# attiny_breakout.net
KiCad netlist of a schematic drawn in EAGLE
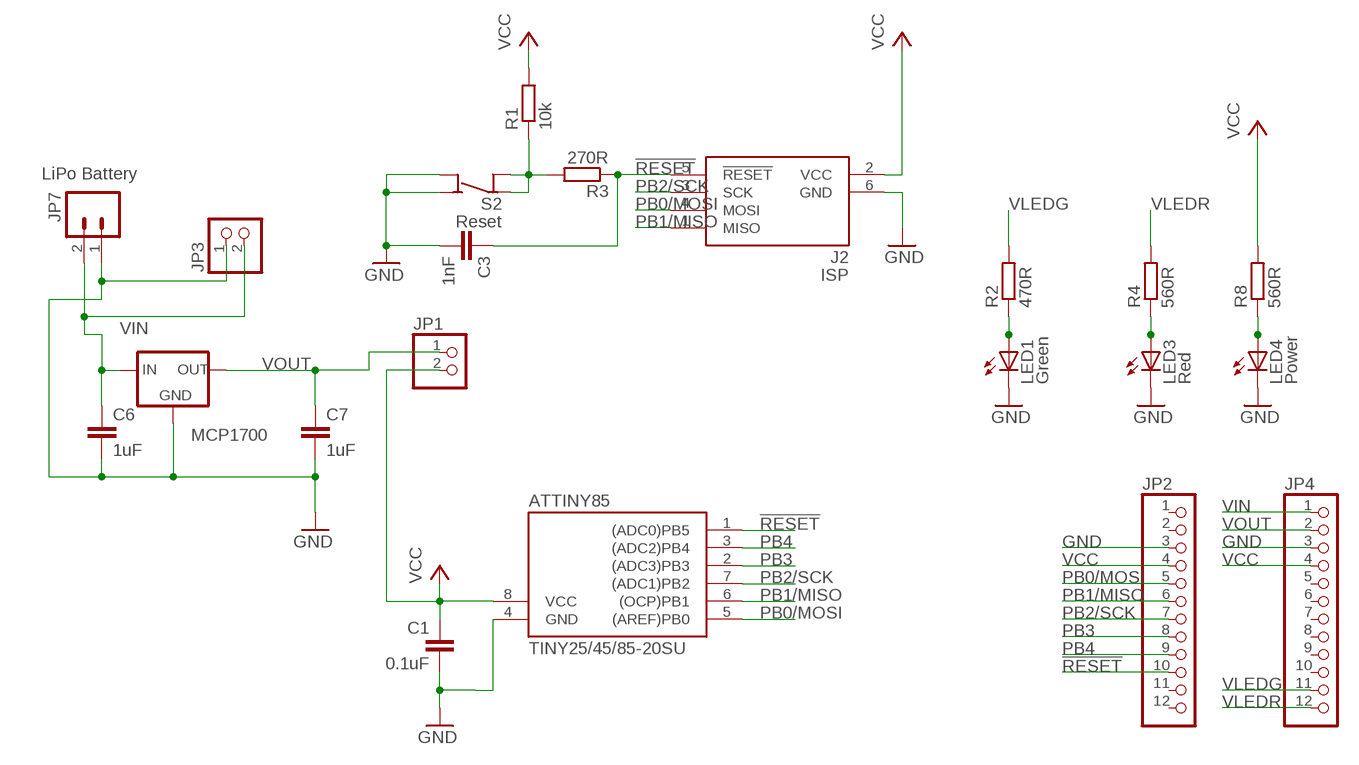
[diagram p0: schematic, sheet 1]

(export (version "E")
  (design (tool "Eeschema 10.0.6"))
  (components
    (comp (ref "ATTINY85")
      (value "TINY25/45/85-20SU")
      (footprint "eagle-import:SOIC8")
      (libsource (lib "eagle-import") (part "TINY25/45/85-20SU"))
    )
    (comp (ref "C1")
      (value "0.1uF")
      (footprint "eagle-import:C0805")
      (libsource (lib "eagle-import") (part "C-EUC0805"))
    )
    (comp (ref "C3")
      (value "1nF")
      (footprint "eagle-import:C0805")
      (libsource (lib "eagle-import") (part "C-EUC0805"))
    )
    (comp (ref "C6")
      (value "1uF")
      (footprint "eagle-import:C0805")
      (libsource (lib "eagle-import") (part "C-EUC0805"))
    )
    (comp (ref "C7")
      (value "1uF")
      (footprint "eagle-import:C0805")
      (libsource (lib "eagle-import") (part "C-EUC0805"))
    )
    (comp (ref "J2")
      (value "ISP")
      (footprint "eagle-import:CON6P2R")
      (libsource (lib "eagle-import") (part "AVRISP6"))
    )
    (comp (ref "JP1")
      (value "PINHD-1X2")
      (footprint "eagle-import:1X02")
      (libsource (lib "eagle-import") (part "PINHD-1X2"))
    )
    (comp (ref "JP2")
      (value "PINHD-1X12")
      (footprint "eagle-import:1X12")
      (libsource (lib "eagle-import") (part "PINHD-1X12"))
    )
    (comp (ref "JP3")
      (value "PINHD-1X2")
      (footprint "eagle-import:1X02")
      (libsource (lib "eagle-import") (part "PINHD-1X2"))
    )
    (comp (ref "JP4")
      (value "PINHD-1X12")
      (footprint "eagle-import:1X12")
      (libsource (lib "eagle-import") (part "PINHD-1X12"))
    )
    (comp (ref "JP7")
      (value "LiPo Battery")
      (footprint "eagle-import:JST-2-PTH")
      (libsource (lib "eagle-import") (part "M02JST-PTH-2"))
    )
    (comp (ref "LED1")
      (value "Green")
      (footprint "eagle-import:CHIP-LED0805")
      (libsource (lib "eagle-import") (part "LEDCHIP-LED0805"))
    )
    (comp (ref "LED3")
      (value "Red")
      (footprint "eagle-import:CHIP-LED0805")
      (libsource (lib "eagle-import") (part "LEDCHIP-LED0805"))
    )
    (comp (ref "LED4")
      (value "Power")
      (footprint "eagle-import:CHIP-LED0805")
      (libsource (lib "eagle-import") (part "LEDCHIP-LED0805"))
    )
    (comp (ref "MCP1700")
      (value "MCP1700")
      (footprint "eagle-import:SOT-23")
      (libsource (lib "eagle-import") (part "MCP1700SOT-23"))
    )
    (comp (ref "R1")
      (value "10k")
      (footprint "eagle-import:R0805")
      (libsource (lib "eagle-import") (part "R-EU_R0805"))
    )
    (comp (ref "R2")
      (value "470R")
      (footprint "eagle-import:R0805")
      (libsource (lib "eagle-import") (part "R-EU_R0805"))
    )
    (comp (ref "R3")
      (value "270R")
      (footprint "eagle-import:R0805")
      (libsource (lib "eagle-import") (part "R-EU_R0805"))
    )
    (comp (ref "R4")
      (value "560R")
      (footprint "eagle-import:R0805")
      (libsource (lib "eagle-import") (part "R-EU_R0805"))
    )
    (comp (ref "R8")
      (value "560R")
      (footprint "eagle-import:R0805")
      (libsource (lib "eagle-import") (part "R-EU_R0805"))
    )
    (comp (ref "S2")
      (value "Reset")
      (footprint "eagle-import:6MMTACTILE_4PIN")
      (libsource (lib "eagle-import") (part "SPST4"))
    )
  )
  (nets
    (net (code "1") (name "/PB0{slash}MOSI") (class "Default")
      (node (ref "ATTINY85") (pin "5") (pinfunction "(AREF)PB0_5") (pintype "bidirectional"))
      (node (ref "J2") (pin "4") (pinfunction "MOSI_4") (pintype "output"))
      (node (ref "JP2") (pin "5") (pinfunction "5_5") (pintype "passive"))
    )
    (net (code "2") (name "/PB1{slash}MISO") (class "Default")
      (node (ref "ATTINY85") (pin "6") (pinfunction "(OCP)PB1_6") (pintype "bidirectional"))
      (node (ref "J2") (pin "1") (pinfunction "MISO_1") (pintype "input"))
      (node (ref "JP2") (pin "6") (pinfunction "6_6") (pintype "passive"))
    )
    (net (code "3") (name "/PB2{slash}SCK") (class "Default")
      (node (ref "ATTINY85") (pin "7") (pinfunction "(ADC1)PB2_7") (pintype "bidirectional"))
      (node (ref "J2") (pin "3") (pinfunction "SCK_3") (pintype "output"))
      (node (ref "JP2") (pin "7") (pinfunction "7_7") (pintype "passive"))
    )
    (net (code "4") (name "/PB3") (class "Default")
      (node (ref "ATTINY85") (pin "2") (pinfunction "(ADC3)PB3_2") (pintype "bidirectional"))
      (node (ref "JP2") (pin "8") (pinfunction "8_8") (pintype "passive"))
    )
    (net (code "5") (name "/PB4") (class "Default")
      (node (ref "ATTINY85") (pin "3") (pinfunction "(ADC2)PB4_3") (pintype "bidirectional"))
      (node (ref "JP2") (pin "9") (pinfunction "9_9") (pintype "passive"))
    )
    (net (code "6") (name "/VIN") (class "Default")
      (node (ref "C6") (pin "1") (pinfunction "1_1") (pintype "passive"))
      (node (ref "JP3") (pin "2") (pinfunction "2_2") (pintype "passive"))
      (node (ref "JP4") (pin "1") (pinfunction "1_1") (pintype "passive"))
      (node (ref "JP7") (pin "2") (pinfunction "2_2") (pintype "passive"))
      (node (ref "MCP1700") (pin "3") (pinfunction "IN_3") (pintype "input"))
    )
    (net (code "7") (name "/VLEDG") (class "Default")
      (node (ref "JP4") (pin "11") (pinfunction "11_11") (pintype "passive"))
      (node (ref "R2") (pin "2") (pinfunction "2_2") (pintype "passive"))
    )
    (net (code "8") (name "/VLEDR") (class "Default")
      (node (ref "JP4") (pin "12") (pinfunction "12_12") (pintype "passive"))
      (node (ref "R4") (pin "2") (pinfunction "2_2") (pintype "passive"))
    )
    (net (code "9") (name "/VOUT") (class "Default")
      (node (ref "C7") (pin "1") (pinfunction "1_1") (pintype "passive"))
      (node (ref "JP1") (pin "1") (pinfunction "1_1") (pintype "passive"))
      (node (ref "JP4") (pin "2") (pinfunction "2_2") (pintype "passive"))
      (node (ref "MCP1700") (pin "2") (pinfunction "OUT_2") (pintype "passive"))
    )
    (net (code "10") (name "/~{RESET}") (class "Default")
      (node (ref "ATTINY85") (pin "1") (pinfunction "(ADC0)PB5_1") (pintype "bidirectional"))
      (node (ref "C3") (pin "1") (pinfunction "1_1") (pintype "passive"))
      (node (ref "J2") (pin "5") (pinfunction "~{RESET}_5") (pintype "output"))
      (node (ref "JP2") (pin "10") (pinfunction "10_10") (pintype "passive"))
      (node (ref "R3") (pin "1") (pinfunction "1_1") (pintype "passive"))
    )
    (net (code "11") (name "GND") (class "Default")
      (node (ref "ATTINY85") (pin "4") (pinfunction "GND_4") (pintype "power_in"))
      (node (ref "C1") (pin "2") (pinfunction "2_2") (pintype "passive"))
      (node (ref "C3") (pin "2") (pinfunction "2_2") (pintype "passive"))
      (node (ref "C6") (pin "2") (pinfunction "2_2") (pintype "passive"))
      (node (ref "C7") (pin "2") (pinfunction "2_2") (pintype "passive"))
      (node (ref "J2") (pin "6") (pinfunction "GND_6") (pintype "power_in"))
      (node (ref "JP2") (pin "3") (pinfunction "3_3") (pintype "passive"))
      (node (ref "JP3") (pin "1") (pinfunction "1_1") (pintype "passive"))
      (node (ref "JP4") (pin "3") (pinfunction "3_3") (pintype "passive"))
      (node (ref "JP7") (pin "1") (pinfunction "1_1") (pintype "passive"))
      (node (ref "LED1") (pin "C") (pinfunction "C_C") (pintype "passive"))
      (node (ref "LED3") (pin "C") (pinfunction "C_C") (pintype "passive"))
      (node (ref "LED4") (pin "C") (pinfunction "C_C") (pintype "passive"))
      (node (ref "MCP1700") (pin "1") (pinfunction "GND_1") (pintype "input"))
      (node (ref "S2") (pin "A1") (pinfunction "NO_A1") (pintype "passive"))
      (node (ref "S2") (pin "A2") (pinfunction "NO_A2") (pintype "passive"))
    )
    (net (code "12") (name "Net-(LED1-PadA)") (class "Default")
      (node (ref "LED1") (pin "A") (pinfunction "A_A") (pintype "passive"))
      (node (ref "R2") (pin "1") (pinfunction "1_1") (pintype "passive"))
    )
    (net (code "13") (name "Net-(LED3-PadA)") (class "Default")
      (node (ref "LED3") (pin "A") (pinfunction "A_A") (pintype "passive"))
      (node (ref "R4") (pin "1") (pinfunction "1_1") (pintype "passive"))
    )
    (net (code "14") (name "Net-(LED4-PadA)") (class "Default")
      (node (ref "LED4") (pin "A") (pinfunction "A_A") (pintype "passive"))
      (node (ref "R8") (pin "1") (pinfunction "1_1") (pintype "passive"))
    )
    (net (code "15") (name "Net-(R1-Pad1)") (class "Default")
      (node (ref "R1") (pin "1") (pinfunction "1_1") (pintype "passive"))
      (node (ref "R3") (pin "2") (pinfunction "2_2") (pintype "passive"))
      (node (ref "S2") (pin "B1") (pinfunction "COM_B1") (pintype "passive"))
      (node (ref "S2") (pin "B2") (pinfunction "COM_B2") (pintype "passive"))
    )
    (net (code "16") (name "VCC") (class "Default")
      (node (ref "ATTINY85") (pin "8") (pinfunction "VCC_8") (pintype "power_in"))
      (node (ref "C1") (pin "1") (pinfunction "1_1") (pintype "passive"))
      (node (ref "J2") (pin "2") (pinfunction "VCC_2") (pintype "power_in"))
      (node (ref "JP1") (pin "2") (pinfunction "2_2") (pintype "passive"))
      (node (ref "JP2") (pin "4") (pinfunction "4_4") (pintype "passive"))
      (node (ref "JP4") (pin "4") (pinfunction "4_4") (pintype "passive"))
      (node (ref "R1") (pin "2") (pinfunction "2_2") (pintype "passive"))
      (node (ref "R8") (pin "2") (pinfunction "2_2") (pintype "passive"))
    )
    (net (code "17") (name "unconnected-(JP2-Pad1)") (class "Default")
      (node (ref "JP2") (pin "1") (pinfunction "1_1") (pintype "passive"))
    )
    (net (code "18") (name "unconnected-(JP2-Pad2)") (class "Default")
      (node (ref "JP2") (pin "2") (pinfunction "2_2") (pintype "passive"))
    )
    (net (code "19") (name "unconnected-(JP2-Pad11)") (class "Default")
      (node (ref "JP2") (pin "11") (pinfunction "11_11") (pintype "passive"))
    )
    (net (code "20") (name "unconnected-(JP2-Pad12)") (class "Default")
      (node (ref "JP2") (pin "12") (pinfunction "12_12") (pintype "passive"))
    )
    (net (code "21") (name "unconnected-(JP4-Pad5)") (class "Default")
      (node (ref "JP4") (pin "5") (pinfunction "5_5") (pintype "passive"))
    )
    (net (code "22") (name "unconnected-(JP4-Pad6)") (class "Default")
      (node (ref "JP4") (pin "6") (pinfunction "6_6") (pintype "passive"))
    )
    (net (code "23") (name "unconnected-(JP4-Pad7)") (class "Default")
      (node (ref "JP4") (pin "7") (pinfunction "7_7") (pintype "passive"))
    )
    (net (code "24") (name "unconnected-(JP4-Pad8)") (class "Default")
      (node (ref "JP4") (pin "8") (pinfunction "8_8") (pintype "passive"))
    )
    (net (code "25") (name "unconnected-(JP4-Pad9)") (class "Default")
      (node (ref "JP4") (pin "9") (pinfunction "9_9") (pintype "passive"))
    )
    (net (code "26") (name "unconnected-(JP4-Pad10)") (class "Default")
      (node (ref "JP4") (pin "10") (pinfunction "10_10") (pintype "passive"))
    )
  )
)
